# Zeppelin.net
KiCad netlist of a schematic drawn in EAGLE
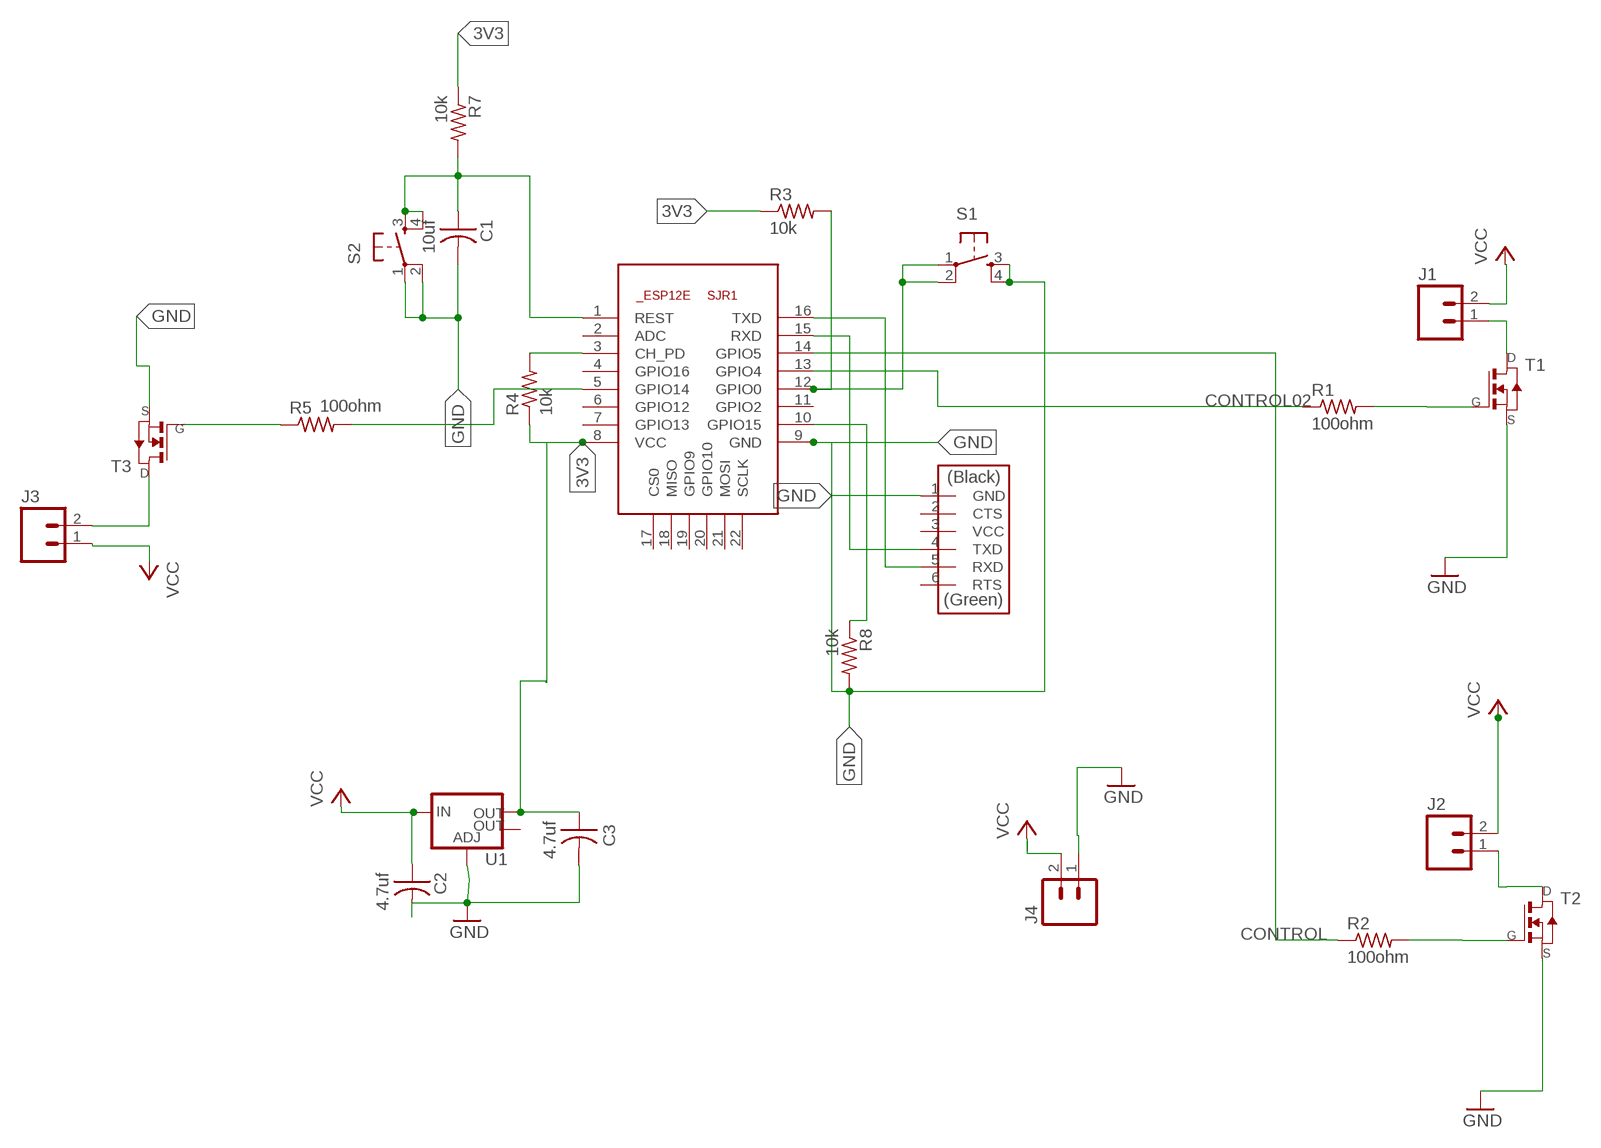
[diagram p0: schematic, sheet 1]

(export (version "E")
  (design (tool "Eeschema 10.0.6"))
  (components
    (comp (ref "C1")
      (value "10uf")
      (footprint "eagle-import:C1206FAB")
      (libsource (lib "eagle-import") (part "CAP-US1206FAB"))
    )
    (comp (ref "C2")
      (value "4.7uf")
      (footprint "eagle-import:C1206FAB")
      (libsource (lib "eagle-import") (part "CAP-US1206FAB"))
    )
    (comp (ref "C3")
      (value "4.7uf")
      (footprint "eagle-import:C1206FAB")
      (libsource (lib "eagle-import") (part "CAP-US1206FAB"))
    )
    (comp (ref "J1")
      (value "M02POLAR_LOCK")
      (footprint "eagle-import:MOLEX-1X2_LOCK")
      (libsource (lib "eagle-import") (part "M02POLAR_LOCK"))
    )
    (comp (ref "J2")
      (value "M02POLAR_LOCK")
      (footprint "eagle-import:MOLEX-1X2_LOCK")
      (libsource (lib "eagle-import") (part "M02POLAR_LOCK"))
    )
    (comp (ref "J3")
      (value "M02POLAR_LOCK")
      (footprint "eagle-import:MOLEX-1X2_LOCK")
      (libsource (lib "eagle-import") (part "M02POLAR_LOCK"))
    )
    (comp (ref "J4")
      (value "M02POLAR_LOCK")
      (footprint "eagle-import:MOLEX-1X2_LOCK")
      (libsource (lib "eagle-import") (part "M02POLAR_LOCK"))
    )
    (comp (ref "R1")
      (value "100ohm")
      (footprint "eagle-import:R1206FAB")
      (libsource (lib "eagle-import") (part "RES-US1206FAB"))
    )
    (comp (ref "R2")
      (value "100ohm")
      (footprint "eagle-import:R1206FAB")
      (libsource (lib "eagle-import") (part "RES-US1206FAB"))
    )
    (comp (ref "R3")
      (value "10k")
      (footprint "eagle-import:R1206FAB")
      (libsource (lib "eagle-import") (part "RES-US1206FAB"))
    )
    (comp (ref "R4")
      (value "10k")
      (footprint "eagle-import:R1206FAB")
      (libsource (lib "eagle-import") (part "RES-US1206FAB"))
    )
    (comp (ref "R5")
      (value "100ohm")
      (footprint "eagle-import:R1206FAB")
      (libsource (lib "eagle-import") (part "RES-US1206FAB"))
    )
    (comp (ref "R7")
      (value "10k")
      (footprint "eagle-import:R1206FAB")
      (libsource (lib "eagle-import") (part "RES-US1206FAB"))
    )
    (comp (ref "R8")
      (value "10k")
      (footprint "eagle-import:R1206FAB")
      (libsource (lib "eagle-import") (part "RES-US1206FAB"))
    )
    (comp (ref "S1")
      (value "6MM_SWITCH6MM_SWITCH")
      (footprint "eagle-import:6MM_SWITCH")
      (libsource (lib "eagle-import") (part "6MM_SWITCH6MM_SWITCH"))
    )
    (comp (ref "S2")
      (value "6MM_SWITCH6MM_SWITCH")
      (footprint "eagle-import:6MM_SWITCH")
      (libsource (lib "eagle-import") (part "6MM_SWITCH6MM_SWITCH"))
    )
    (comp (ref "SJR1")
      (value "ESP8266-12EESP12E")
      (footprint "eagle-import:ESP8266-ESP12E")
      (libsource (lib "eagle-import") (part "ESP8266-12EESP12E"))
    )
    (comp (ref "T1")
      (value "NMOSFETSOT23")
      (footprint "eagle-import:SOT-23")
      (libsource (lib "eagle-import") (part "NMOSFETSOT23"))
    )
    (comp (ref "T2")
      (value "NMOSFETSOT23")
      (footprint "eagle-import:SOT-23")
      (libsource (lib "eagle-import") (part "NMOSFETSOT23"))
    )
    (comp (ref "T3")
      (value "NMOSFETSOT23")
      (footprint "eagle-import:SOT-23")
      (libsource (lib "eagle-import") (part "NMOSFETSOT23"))
    )
    (comp (ref "U$7")
      (value "FTDI-SMD-HEADER")
      (footprint "eagle-import:1X06SMD")
      (libsource (lib "eagle-import") (part "FTDI-SMD-HEADER"))
    )
    (comp (ref "U1")
      (value "V_REG_LM1117SOT223")
      (footprint "eagle-import:SOT223")
      (libsource (lib "eagle-import") (part "V_REG_LM1117SOT223"))
    )
  )
  (nets
    (net (code "1") (name "/CONTROL") (class "Default")
      (node (ref "R2") (pin "1") (pinfunction "1_1") (pintype "passive"))
      (node (ref "SJR1") (pin "14") (pinfunction "GPIO5_14") (pintype "bidirectional"))
    )
    (net (code "2") (name "/CONTROL02") (class "Default")
      (node (ref "R1") (pin "1") (pinfunction "1_1") (pintype "passive"))
      (node (ref "SJR1") (pin "13") (pinfunction "GPIO4_13") (pintype "bidirectional"))
    )
    (net (code "3") (name "3V3") (class "Default")
      (node (ref "C3") (pin "1") (pinfunction "1_1") (pintype "passive"))
      (node (ref "R3") (pin "1") (pinfunction "1_1") (pintype "passive"))
      (node (ref "R4") (pin "1") (pinfunction "1_1") (pintype "passive"))
      (node (ref "R7") (pin "1") (pinfunction "1_1") (pintype "passive"))
      (node (ref "SJR1") (pin "8") (pinfunction "VCC_8") (pintype "bidirectional"))
      (node (ref "U1") (pin "2") (pinfunction "OUT_2") (pintype "output"))
    )
    (net (code "4") (name "GND") (class "Default")
      (node (ref "C1") (pin "2") (pinfunction "2_2") (pintype "passive"))
      (node (ref "C2") (pin "2") (pinfunction "2_2") (pintype "passive"))
      (node (ref "C3") (pin "2") (pinfunction "2_2") (pintype "passive"))
      (node (ref "J4") (pin "1") (pinfunction "1_1") (pintype "passive"))
      (node (ref "R8") (pin "2") (pinfunction "2_2") (pintype "passive"))
      (node (ref "S1") (pin "3") (pinfunction "S_3") (pintype "passive"))
      (node (ref "S1") (pin "4") (pinfunction "S1_4") (pintype "passive"))
      (node (ref "S2") (pin "1") (pinfunction "P_1") (pintype "passive"))
      (node (ref "S2") (pin "2") (pinfunction "P1_2") (pintype "passive"))
      (node (ref "SJR1") (pin "9") (pinfunction "GND_9") (pintype "bidirectional"))
      (node (ref "T1") (pin "2") (pinfunction "S_2") (pintype "passive"))
      (node (ref "T2") (pin "2") (pinfunction "S_2") (pintype "passive"))
      (node (ref "T3") (pin "2") (pinfunction "S_2") (pintype "passive"))
      (node (ref "U$7") (pin "1") (pinfunction "GND_1") (pintype "bidirectional"))
      (node (ref "U1") (pin "1") (pinfunction "ADJ_1") (pintype "input"))
    )
    (net (code "5") (name "Net-(S1-P)") (class "Default")
      (node (ref "R3") (pin "2") (pinfunction "2_2") (pintype "passive"))
      (node (ref "S1") (pin "1") (pinfunction "P_1") (pintype "passive"))
      (node (ref "S1") (pin "2") (pinfunction "P1_2") (pintype "passive"))
      (node (ref "SJR1") (pin "12") (pinfunction "GPIO0_12") (pintype "bidirectional"))
    )
    (net (code "6") (name "Net-(S2-S)") (class "Default")
      (node (ref "C1") (pin "1") (pinfunction "1_1") (pintype "passive"))
      (node (ref "R7") (pin "2") (pinfunction "2_2") (pintype "passive"))
      (node (ref "S2") (pin "3") (pinfunction "S_3") (pintype "passive"))
      (node (ref "S2") (pin "4") (pinfunction "S1_4") (pintype "passive"))
      (node (ref "SJR1") (pin "1") (pinfunction "REST_1") (pintype "bidirectional"))
    )
    (net (code "7") (name "Net-(SJR1-CH_PD)") (class "Default")
      (node (ref "R4") (pin "2") (pinfunction "2_2") (pintype "passive"))
      (node (ref "SJR1") (pin "3") (pinfunction "CH_PD_3") (pintype "bidirectional"))
    )
    (net (code "8") (name "Net-(SJR1-GPIO14)") (class "Default")
      (node (ref "R5") (pin "2") (pinfunction "2_2") (pintype "passive"))
      (node (ref "SJR1") (pin "5") (pinfunction "GPIO14_5") (pintype "bidirectional"))
    )
    (net (code "9") (name "Net-(SJR1-GPIO15)") (class "Default")
      (node (ref "R8") (pin "1") (pinfunction "1_1") (pintype "passive"))
      (node (ref "SJR1") (pin "10") (pinfunction "GPIO15_10") (pintype "bidirectional"))
    )
    (net (code "10") (name "Net-(SJR1-RXD)") (class "Default")
      (node (ref "SJR1") (pin "15") (pinfunction "RXD_15") (pintype "bidirectional"))
      (node (ref "U$7") (pin "4") (pinfunction "TXD_4") (pintype "bidirectional"))
    )
    (net (code "11") (name "Net-(SJR1-TXD)") (class "Default")
      (node (ref "SJR1") (pin "16") (pinfunction "TXD_16") (pintype "bidirectional"))
      (node (ref "U$7") (pin "5") (pinfunction "RXD_5") (pintype "bidirectional"))
    )
    (net (code "12") (name "Net-(T1-D)") (class "Default")
      (node (ref "J1") (pin "1") (pinfunction "1_1") (pintype "passive"))
      (node (ref "T1") (pin "1") (pinfunction "D_1") (pintype "passive"))
    )
    (net (code "13") (name "Net-(T1-G)") (class "Default")
      (node (ref "R1") (pin "2") (pinfunction "2_2") (pintype "passive"))
      (node (ref "T1") (pin "3") (pinfunction "G_3") (pintype "passive"))
    )
    (net (code "14") (name "Net-(T2-D)") (class "Default")
      (node (ref "J2") (pin "1") (pinfunction "1_1") (pintype "passive"))
      (node (ref "T2") (pin "1") (pinfunction "D_1") (pintype "passive"))
    )
    (net (code "15") (name "Net-(T2-G)") (class "Default")
      (node (ref "R2") (pin "2") (pinfunction "2_2") (pintype "passive"))
      (node (ref "T2") (pin "3") (pinfunction "G_3") (pintype "passive"))
    )
    (net (code "16") (name "Net-(T3-D)") (class "Default")
      (node (ref "J3") (pin "2") (pinfunction "2_2") (pintype "passive"))
      (node (ref "T3") (pin "1") (pinfunction "D_1") (pintype "passive"))
    )
    (net (code "17") (name "Net-(T3-G)") (class "Default")
      (node (ref "R5") (pin "1") (pinfunction "1_1") (pintype "passive"))
      (node (ref "T3") (pin "3") (pinfunction "G_3") (pintype "passive"))
    )
    (net (code "18") (name "VCC") (class "Default")
      (node (ref "C2") (pin "1") (pinfunction "1_1") (pintype "passive"))
      (node (ref "J1") (pin "2") (pinfunction "2_2") (pintype "passive"))
      (node (ref "J2") (pin "2") (pinfunction "2_2") (pintype "passive"))
      (node (ref "J3") (pin "1") (pinfunction "1_1") (pintype "passive"))
      (node (ref "J4") (pin "2") (pinfunction "2_2") (pintype "passive"))
      (node (ref "U1") (pin "3") (pinfunction "IN_3") (pintype "input"))
    )
    (net (code "19") (name "unconnected-(SJR1-ADC-Pad2)") (class "Default")
      (node (ref "SJR1") (pin "2") (pinfunction "ADC_2") (pintype "bidirectional"))
    )
    (net (code "20") (name "unconnected-(SJR1-CS0-Pad17)") (class "Default")
      (node (ref "SJR1") (pin "17") (pinfunction "CS0_17") (pintype "bidirectional"))
    )
    (net (code "21") (name "unconnected-(SJR1-GPIO2-Pad11)") (class "Default")
      (node (ref "SJR1") (pin "11") (pinfunction "GPIO2_11") (pintype "bidirectional"))
    )
    (net (code "22") (name "unconnected-(SJR1-GPIO9-Pad19)") (class "Default")
      (node (ref "SJR1") (pin "19") (pinfunction "GPIO9_19") (pintype "bidirectional"))
    )
    (net (code "23") (name "unconnected-(SJR1-GPIO10-Pad20)") (class "Default")
      (node (ref "SJR1") (pin "20") (pinfunction "GPIO10_20") (pintype "bidirectional"))
    )
    (net (code "24") (name "unconnected-(SJR1-GPIO12-Pad6)") (class "Default")
      (node (ref "SJR1") (pin "6") (pinfunction "GPIO12_6") (pintype "bidirectional"))
    )
    (net (code "25") (name "unconnected-(SJR1-GPIO13-Pad7)") (class "Default")
      (node (ref "SJR1") (pin "7") (pinfunction "GPIO13_7") (pintype "bidirectional"))
    )
    (net (code "26") (name "unconnected-(SJR1-GPIO16-Pad4)") (class "Default")
      (node (ref "SJR1") (pin "4") (pinfunction "GPIO16_4") (pintype "bidirectional"))
    )
    (net (code "27") (name "unconnected-(SJR1-MISO-Pad18)") (class "Default")
      (node (ref "SJR1") (pin "18") (pinfunction "MISO_18") (pintype "bidirectional"))
    )
    (net (code "28") (name "unconnected-(SJR1-MOSI-Pad21)") (class "Default")
      (node (ref "SJR1") (pin "21") (pinfunction "MOSI_21") (pintype "bidirectional"))
    )
    (net (code "29") (name "unconnected-(SJR1-SCLK-Pad22)") (class "Default")
      (node (ref "SJR1") (pin "22") (pinfunction "SCLK_22") (pintype "bidirectional"))
    )
    (net (code "30") (name "unconnected-(U$7-CTS-Pad2)") (class "Default")
      (node (ref "U$7") (pin "2") (pinfunction "CTS_2") (pintype "bidirectional"))
    )
    (net (code "31") (name "unconnected-(U$7-RTS-Pad6)") (class "Default")
      (node (ref "U$7") (pin "6") (pinfunction "RTS_6") (pintype "bidirectional"))
    )
    (net (code "32") (name "unconnected-(U$7-VCC-Pad3)") (class "Default")
      (node (ref "U$7") (pin "3") (pinfunction "VCC_3") (pintype "bidirectional"))
    )
    (net (code "33") (name "unconnected-(U1-OUT-Pad4)") (class "Default")
      (node (ref "U1") (pin "4") (pinfunction "OUT_4") (pintype "output"))
    )
  )
)
